# bms_board.net
KiCad netlist of a schematic drawn in EAGLE
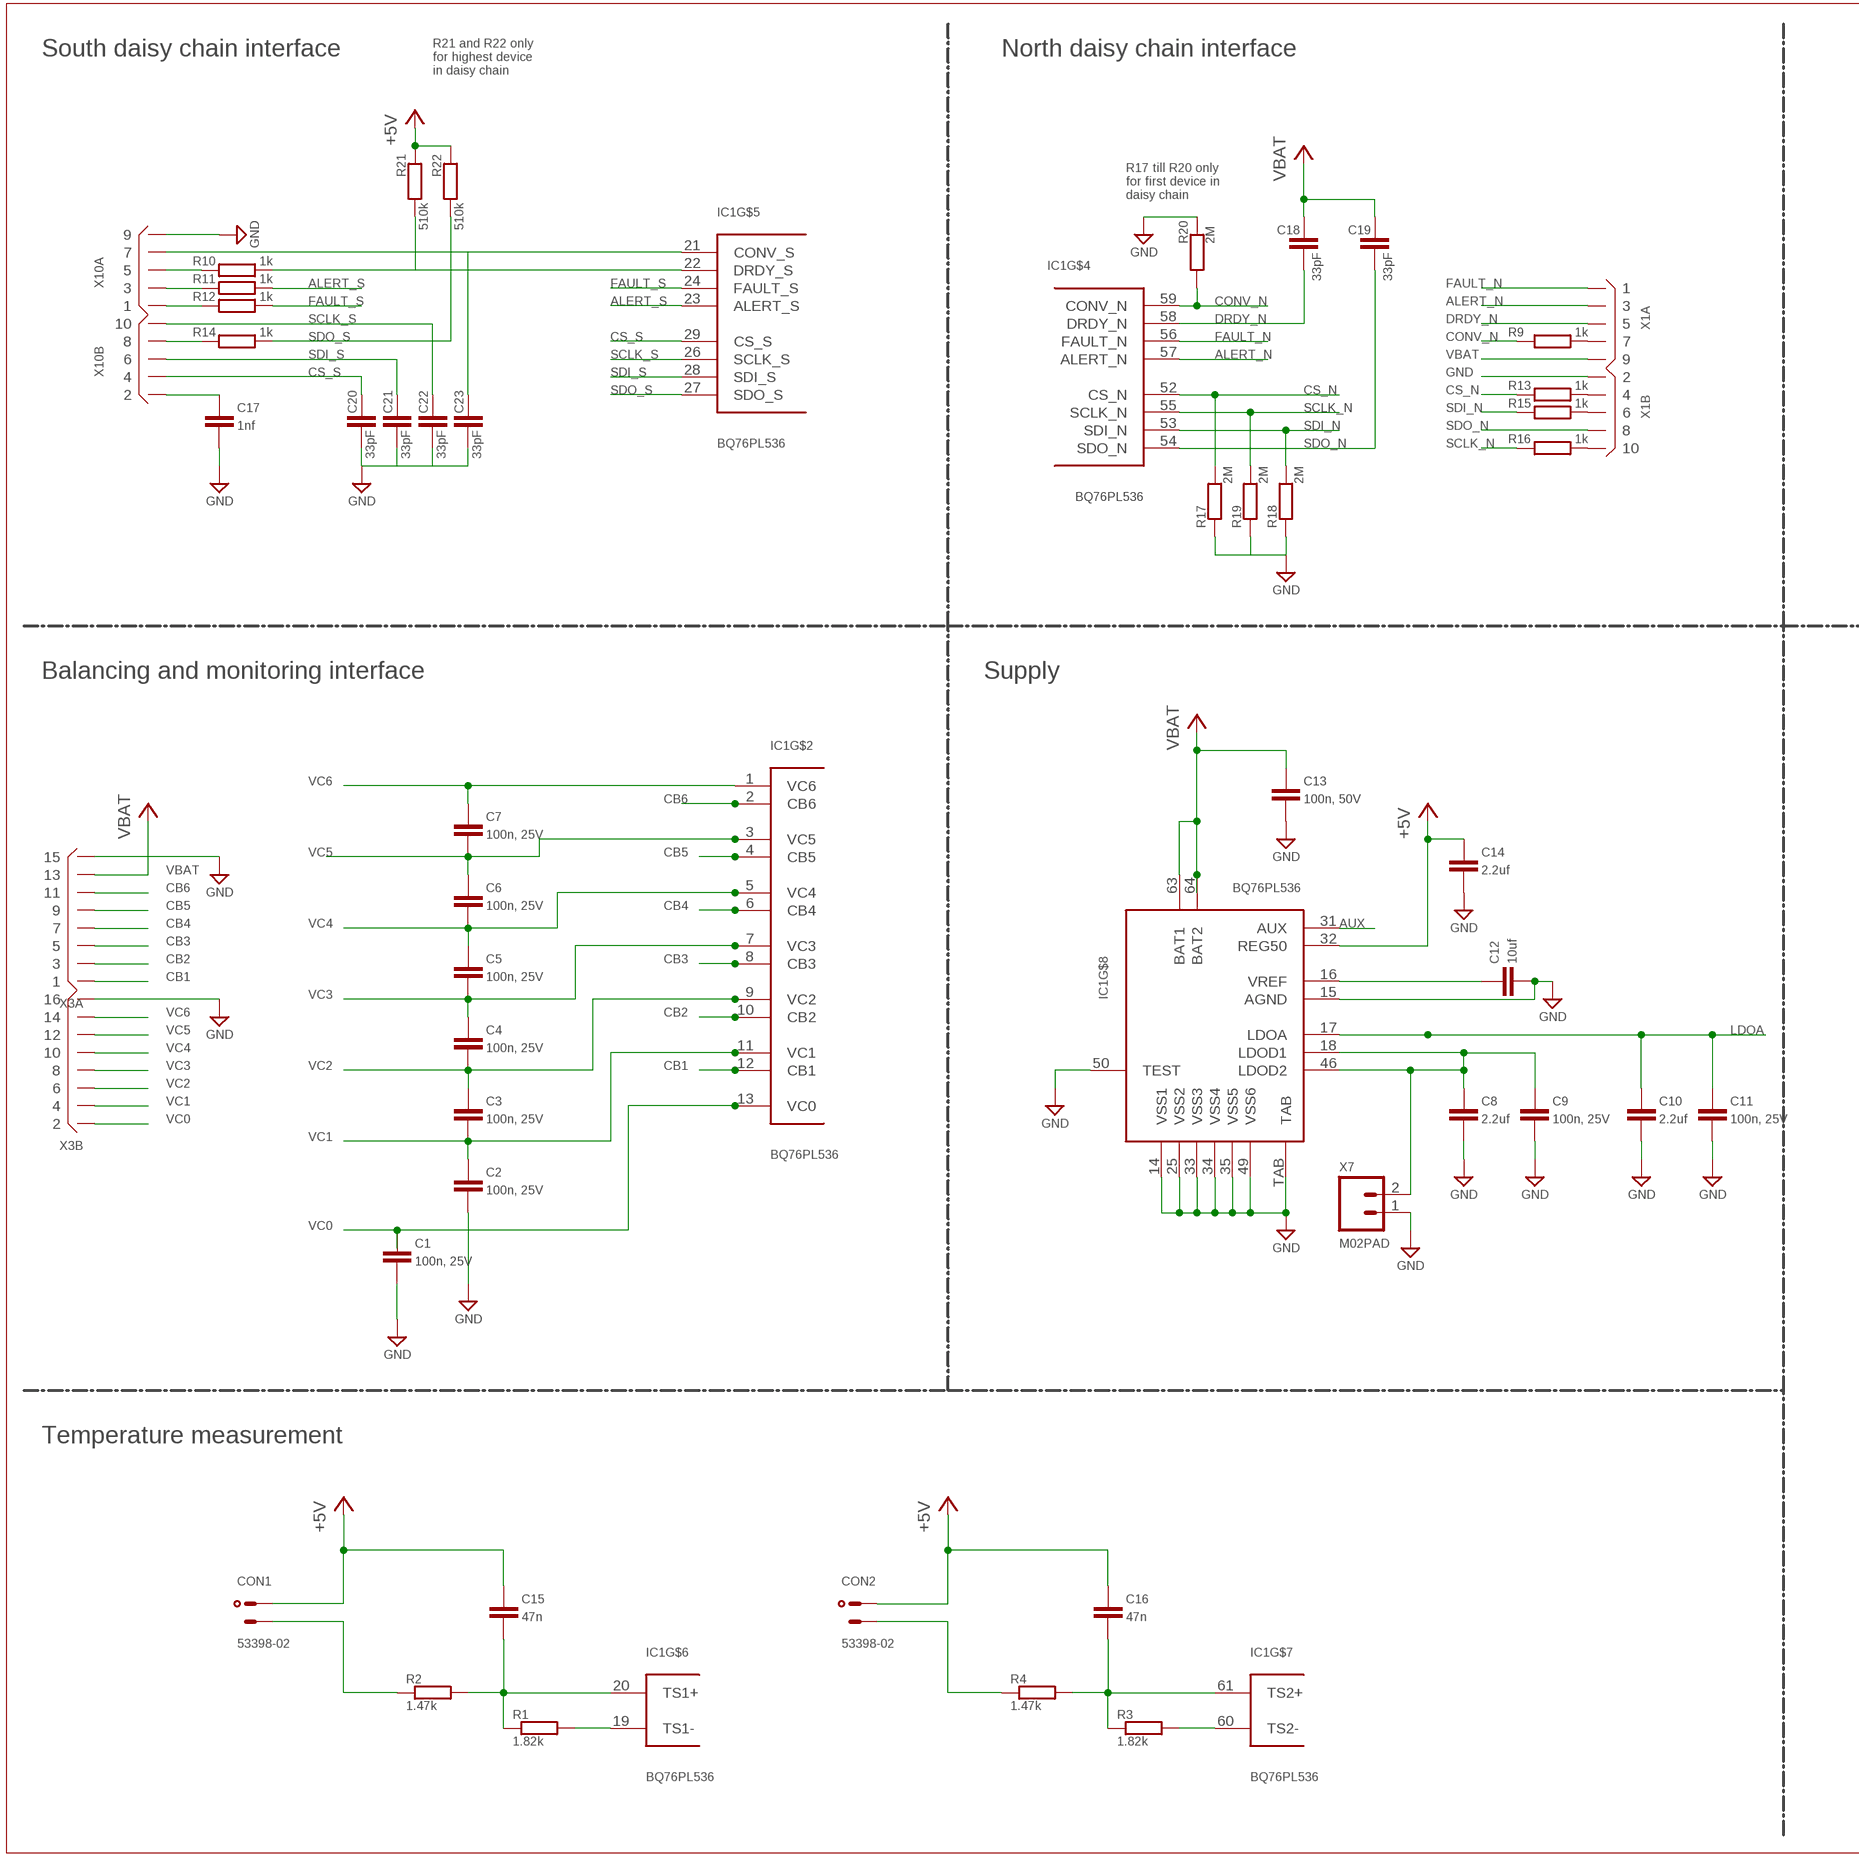
[diagram p0: schematic, sheet 1, part 1 of 2]
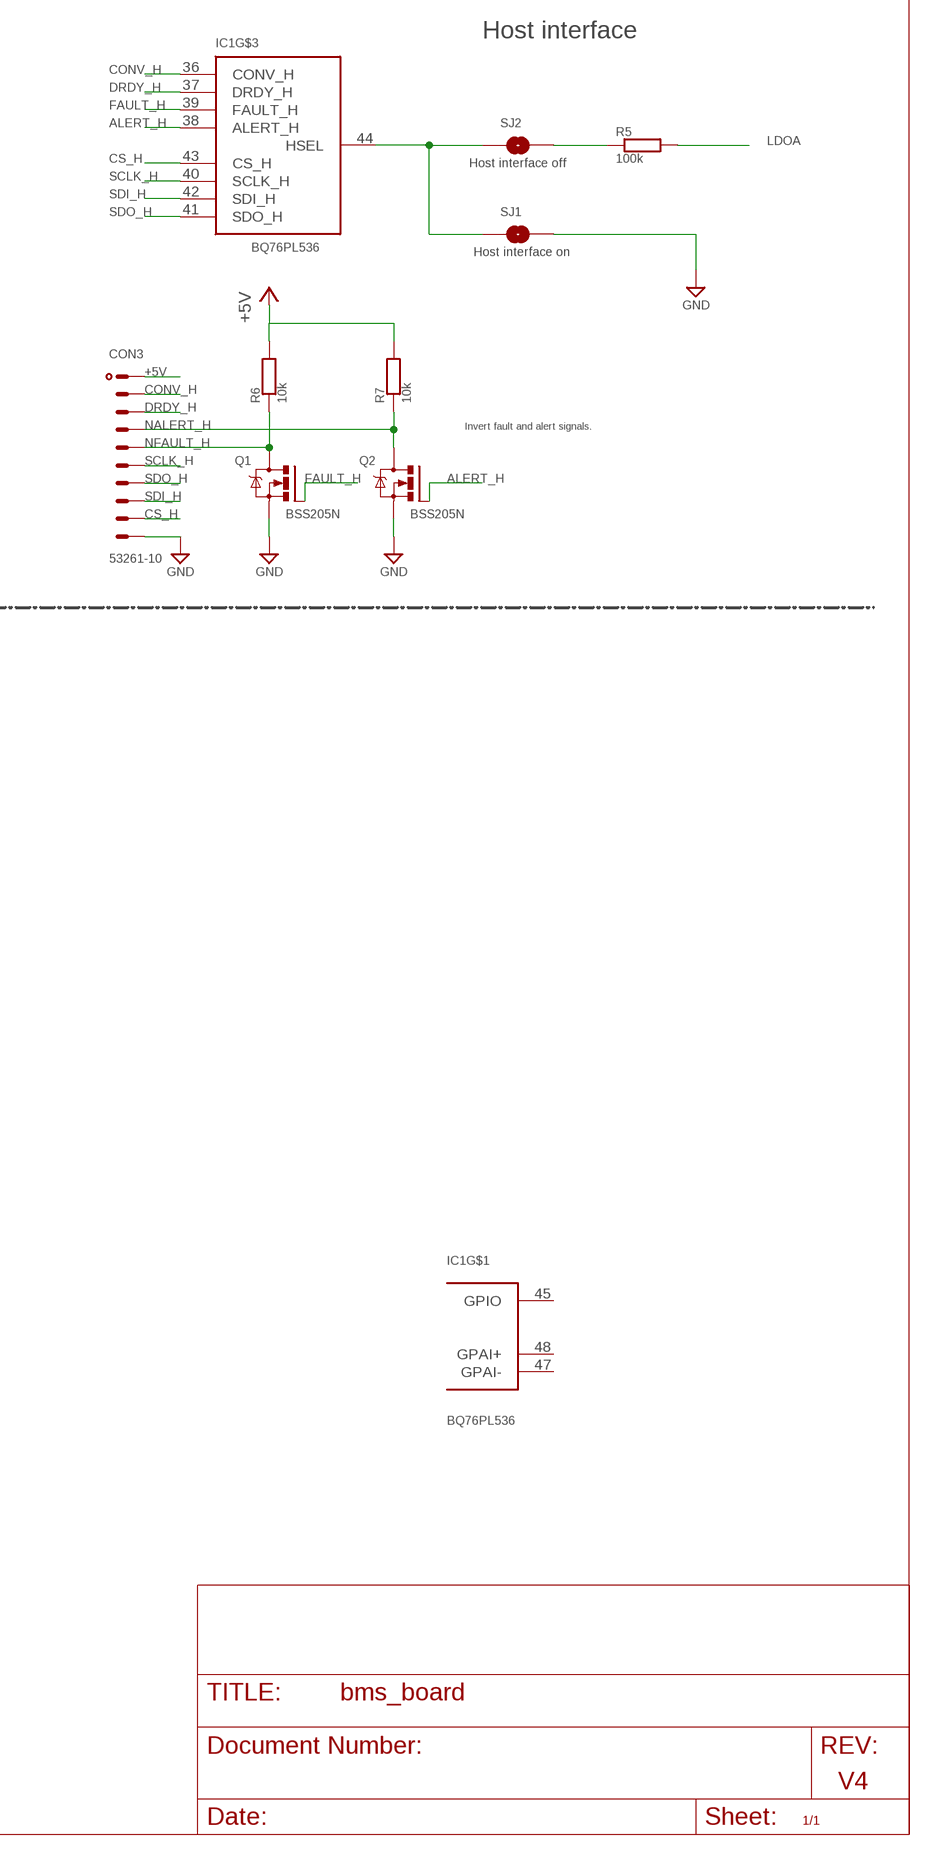
[diagram p1: schematic, sheet 1, part 2 of 2]

(export (version "E")
  (design (tool "Eeschema 10.0.6"))
  (components
    (comp (ref "C1")
      (value "100n, 25V")
      (footprint "eagle-import:C0603")
      (libsource (lib "eagle-import") (part "C0603"))
    )
    (comp (ref "C2")
      (value "100n, 25V")
      (footprint "eagle-import:C0603")
      (libsource (lib "eagle-import") (part "C0603"))
    )
    (comp (ref "C3")
      (value "100n, 25V")
      (footprint "eagle-import:C0603")
      (libsource (lib "eagle-import") (part "C0603"))
    )
    (comp (ref "C4")
      (value "100n, 25V")
      (footprint "eagle-import:C0603")
      (libsource (lib "eagle-import") (part "C0603"))
    )
    (comp (ref "C5")
      (value "100n, 25V")
      (footprint "eagle-import:C0603")
      (libsource (lib "eagle-import") (part "C0603"))
    )
    (comp (ref "C6")
      (value "100n, 25V")
      (footprint "eagle-import:C0603")
      (libsource (lib "eagle-import") (part "C0603"))
    )
    (comp (ref "C7")
      (value "100n, 25V")
      (footprint "eagle-import:C0603")
      (libsource (lib "eagle-import") (part "C0603"))
    )
    (comp (ref "C8")
      (value "2.2uf")
      (footprint "eagle-import:C0805")
      (libsource (lib "eagle-import") (part "CSTD"))
    )
    (comp (ref "C9")
      (value "100n, 25V")
      (footprint "eagle-import:C0805")
      (libsource (lib "eagle-import") (part "CSTD"))
    )
    (comp (ref "C10")
      (value "2.2uf")
      (footprint "eagle-import:C0805")
      (libsource (lib "eagle-import") (part "CSTD"))
    )
    (comp (ref "C11")
      (value "100n, 25V")
      (footprint "eagle-import:C0805")
      (libsource (lib "eagle-import") (part "CSTD"))
    )
    (comp (ref "C12")
      (value "10uf")
      (footprint "eagle-import:C0805")
      (libsource (lib "eagle-import") (part "CSTD"))
    )
    (comp (ref "C13")
      (value "100n, 50V")
      (footprint "eagle-import:C0805")
      (libsource (lib "eagle-import") (part "CSTD"))
    )
    (comp (ref "C14")
      (value "2.2uf")
      (footprint "eagle-import:C0805")
      (libsource (lib "eagle-import") (part "CSTD"))
    )
    (comp (ref "C15")
      (value "47n")
      (footprint "eagle-import:C0805")
      (libsource (lib "eagle-import") (part "CSTD"))
    )
    (comp (ref "C16")
      (value "47n")
      (footprint "eagle-import:C0805")
      (libsource (lib "eagle-import") (part "CSTD"))
    )
    (comp (ref "C17")
      (value "1nf")
      (footprint "eagle-import:C0805")
      (libsource (lib "eagle-import") (part "CSTD"))
    )
    (comp (ref "C18")
      (value "33pF")
      (footprint "eagle-import:C0603")
      (libsource (lib "eagle-import") (part "C0603"))
    )
    (comp (ref "C19")
      (value "33pF")
      (footprint "eagle-import:C0603")
      (libsource (lib "eagle-import") (part "C0603"))
    )
    (comp (ref "C20")
      (value "33pF")
      (footprint "eagle-import:C0603")
      (libsource (lib "eagle-import") (part "C0603"))
    )
    (comp (ref "C21")
      (value "33pF")
      (footprint "eagle-import:C0603")
      (libsource (lib "eagle-import") (part "C0603"))
    )
    (comp (ref "C22")
      (value "33pF")
      (footprint "eagle-import:C0603")
      (libsource (lib "eagle-import") (part "C0603"))
    )
    (comp (ref "C23")
      (value "33pF")
      (footprint "eagle-import:C0603")
      (libsource (lib "eagle-import") (part "C0603"))
    )
    (comp (ref "CON1")
      (value "53398-02")
      (footprint "eagle-import:53398-02")
      (libsource (lib "eagle-import") (part "53?-02398"))
    )
    (comp (ref "CON2")
      (value "53398-02")
      (footprint "eagle-import:53398-02")
      (libsource (lib "eagle-import") (part "53?-02398"))
    )
    (comp (ref "CON3")
      (value "53261-10")
      (footprint "eagle-import:53261-10")
      (libsource (lib "eagle-import") (part "53?-10261"))
    )
    (comp (ref "IC1")
      (value "BQ76PL536")
      (footprint "eagle-import:LQFP-64")
      (libsource (lib "eagle-import") (part "BQ76PL536"))
    )
    (comp (ref "Q1")
      (value "BSS205N")
      (footprint "eagle-import:SOT23")
      (libsource (lib "eagle-import") (part "BSS205N"))
    )
    (comp (ref "Q2")
      (value "BSS205N")
      (footprint "eagle-import:SOT23")
      (libsource (lib "eagle-import") (part "BSS205N"))
    )
    (comp (ref "R1")
      (value "1.82k")
      (footprint "eagle-import:R0805")
      (libsource (lib "eagle-import") (part "R"))
    )
    (comp (ref "R2")
      (value "1.47k")
      (footprint "eagle-import:R0805")
      (libsource (lib "eagle-import") (part "R"))
    )
    (comp (ref "R3")
      (value "1.82k")
      (footprint "eagle-import:R0805")
      (libsource (lib "eagle-import") (part "R"))
    )
    (comp (ref "R4")
      (value "1.47k")
      (footprint "eagle-import:R0805")
      (libsource (lib "eagle-import") (part "R"))
    )
    (comp (ref "R5")
      (value "100k")
      (footprint "eagle-import:R0805")
      (libsource (lib "eagle-import") (part "R"))
    )
    (comp (ref "R6")
      (value "10k")
      (footprint "eagle-import:R0805")
      (libsource (lib "eagle-import") (part "R"))
    )
    (comp (ref "R7")
      (value "10k")
      (footprint "eagle-import:R0805")
      (libsource (lib "eagle-import") (part "R"))
    )
    (comp (ref "R9")
      (value "1k")
      (footprint "eagle-import:R0603")
      (libsource (lib "eagle-import") (part "R0603"))
    )
    (comp (ref "R10")
      (value "1k")
      (footprint "eagle-import:R0603")
      (libsource (lib "eagle-import") (part "R0603"))
    )
    (comp (ref "R11")
      (value "1k")
      (footprint "eagle-import:R0603")
      (libsource (lib "eagle-import") (part "R0603"))
    )
    (comp (ref "R12")
      (value "1k")
      (footprint "eagle-import:R0603")
      (libsource (lib "eagle-import") (part "R0603"))
    )
    (comp (ref "R13")
      (value "1k")
      (footprint "eagle-import:R0603")
      (libsource (lib "eagle-import") (part "R0603"))
    )
    (comp (ref "R14")
      (value "1k")
      (footprint "eagle-import:R0603")
      (libsource (lib "eagle-import") (part "R0603"))
    )
    (comp (ref "R15")
      (value "1k")
      (footprint "eagle-import:R0603")
      (libsource (lib "eagle-import") (part "R0603"))
    )
    (comp (ref "R16")
      (value "1k")
      (footprint "eagle-import:R0603")
      (libsource (lib "eagle-import") (part "R0603"))
    )
    (comp (ref "R17")
      (value "2M")
      (footprint "eagle-import:R0603")
      (libsource (lib "eagle-import") (part "R0603"))
    )
    (comp (ref "R18")
      (value "2M")
      (footprint "eagle-import:R0603")
      (libsource (lib "eagle-import") (part "R0603"))
    )
    (comp (ref "R19")
      (value "2M")
      (footprint "eagle-import:R0603")
      (libsource (lib "eagle-import") (part "R0603"))
    )
    (comp (ref "R20")
      (value "2M")
      (footprint "eagle-import:R0603")
      (libsource (lib "eagle-import") (part "R0603"))
    )
    (comp (ref "R21")
      (value "510k")
      (footprint "eagle-import:R0603")
      (libsource (lib "eagle-import") (part "R0603"))
    )
    (comp (ref "R22")
      (value "510k")
      (footprint "eagle-import:R0603")
      (libsource (lib "eagle-import") (part "R0603"))
    )
    (comp (ref "SJ1")
      (value "SOLDERJUMPERNO")
      (footprint "eagle-import:SJ_2S-NO")
      (libsource (lib "eagle-import") (part "SOLDERJUMPERNO"))
    )
    (comp (ref "SJ2")
      (value "SOLDERJUMPERNO")
      (footprint "eagle-import:SJ_2S-NO")
      (libsource (lib "eagle-import") (part "SOLDERJUMPERNO"))
    )
    (comp (ref "X1")
      (value "X05X2IDC-H")
      (footprint "eagle-import:X10R-IDC-H")
      (libsource (lib "eagle-import") (part "X05X2IDC-H"))
    )
    (comp (ref "X3")
      (value "X08X2DR")
      (footprint "eagle-import:X16R-DIL")
      (libsource (lib "eagle-import") (part "X08X2DR"))
    )
    (comp (ref "X7")
      (value "M02PAD")
      (footprint "eagle-import:1X02")
      (libsource (lib "eagle-import") (part "M02PAD"))
    )
    (comp (ref "X10")
      (value "X05X2IDC-H")
      (footprint "eagle-import:X10R-IDC-H")
      (libsource (lib "eagle-import") (part "X05X2IDC-H"))
    )
  )
  (nets
    (net (code "1") (name "+5V") (class "Default")
      (node (ref "C14") (pin "2") (pinfunction "2_2") (pintype "passive"))
      (node (ref "C15") (pin "2") (pinfunction "2_2") (pintype "passive"))
      (node (ref "C16") (pin "2") (pinfunction "2_2") (pintype "passive"))
      (node (ref "CON1") (pin "1") (pinfunction "1_1") (pintype "passive"))
      (node (ref "CON2") (pin "1") (pinfunction "1_1") (pintype "passive"))
      (node (ref "CON3") (pin "1") (pinfunction "1_1") (pintype "passive"))
      (node (ref "IC1") (pin "32") (pinfunction "REG50_32") (pintype "bidirectional"))
      (node (ref "R21") (pin "2") (pinfunction "2_2") (pintype "passive"))
      (node (ref "R22") (pin "2") (pinfunction "2_2") (pintype "passive"))
      (node (ref "R6") (pin "2") (pinfunction "2_2") (pintype "passive"))
      (node (ref "R7") (pin "2") (pinfunction "2_2") (pintype "passive"))
    )
    (net (code "2") (name "/ALERT_H") (class "Default")
      (node (ref "IC1") (pin "38") (pinfunction "ALERT_H_38") (pintype "bidirectional"))
      (node (ref "Q2") (pin "1") (pinfunction "G_1") (pintype "passive"))
    )
    (net (code "3") (name "/ALERT_N") (class "Default")
      (node (ref "IC1") (pin "57") (pinfunction "ALERT_N_57") (pintype "bidirectional"))
      (node (ref "X1") (pin "3") (pinfunction "3_3") (pintype "bidirectional"))
    )
    (net (code "4") (name "/ALERT_S") (class "Default")
      (node (ref "IC1") (pin "23") (pinfunction "ALERT_S_23") (pintype "bidirectional"))
      (node (ref "R11") (pin "2") (pinfunction "2_2") (pintype "passive"))
    )
    (net (code "5") (name "/AUX") (class "Default")
      (node (ref "IC1") (pin "31") (pinfunction "AUX_31") (pintype "bidirectional"))
    )
    (net (code "6") (name "/CB1") (class "Default")
      (node (ref "IC1") (pin "12") (pinfunction "CB1_12") (pintype "bidirectional"))
      (node (ref "X3") (pin "1") (pinfunction "1_1") (pintype "bidirectional"))
    )
    (net (code "7") (name "/CB2") (class "Default")
      (node (ref "IC1") (pin "10") (pinfunction "CB2_10") (pintype "bidirectional"))
      (node (ref "X3") (pin "3") (pinfunction "3_3") (pintype "bidirectional"))
    )
    (net (code "8") (name "/CB3") (class "Default")
      (node (ref "IC1") (pin "8") (pinfunction "CB3_8") (pintype "bidirectional"))
      (node (ref "X3") (pin "5") (pinfunction "5_5") (pintype "bidirectional"))
    )
    (net (code "9") (name "/CB4") (class "Default")
      (node (ref "IC1") (pin "6") (pinfunction "CB4_6") (pintype "bidirectional"))
      (node (ref "X3") (pin "7") (pinfunction "7_7") (pintype "bidirectional"))
    )
    (net (code "10") (name "/CB5") (class "Default")
      (node (ref "IC1") (pin "4") (pinfunction "CB5_4") (pintype "bidirectional"))
      (node (ref "X3") (pin "9") (pinfunction "9_9") (pintype "bidirectional"))
    )
    (net (code "11") (name "/CB6") (class "Default")
      (node (ref "IC1") (pin "2") (pinfunction "CB6_2") (pintype "bidirectional"))
      (node (ref "X3") (pin "11") (pinfunction "11_11") (pintype "bidirectional"))
    )
    (net (code "12") (name "/CONV_H") (class "Default")
      (node (ref "CON3") (pin "2") (pinfunction "2_2") (pintype "passive"))
      (node (ref "IC1") (pin "36") (pinfunction "CONV_H_36") (pintype "bidirectional"))
    )
    (net (code "13") (name "/CONV_N") (class "Default")
      (node (ref "IC1") (pin "59") (pinfunction "CONV_N_59") (pintype "bidirectional"))
      (node (ref "R20") (pin "2") (pinfunction "2_2") (pintype "passive"))
      (node (ref "R9") (pin "1") (pinfunction "1_1") (pintype "passive"))
    )
    (net (code "14") (name "/CS_H") (class "Default")
      (node (ref "CON3") (pin "9") (pinfunction "9_9") (pintype "passive"))
      (node (ref "IC1") (pin "43") (pinfunction "CS_H_43") (pintype "bidirectional"))
    )
    (net (code "15") (name "/CS_N") (class "Default")
      (node (ref "IC1") (pin "52") (pinfunction "CS_N_52") (pintype "bidirectional"))
      (node (ref "R13") (pin "1") (pinfunction "1_1") (pintype "passive"))
      (node (ref "R17") (pin "2") (pinfunction "2_2") (pintype "passive"))
    )
    (net (code "16") (name "/CS_S") (class "Default")
      (node (ref "C20") (pin "1") (pinfunction "1_1") (pintype "passive"))
      (node (ref "IC1") (pin "29") (pinfunction "CS_S_29") (pintype "bidirectional"))
      (node (ref "X10") (pin "4") (pinfunction "4_4") (pintype "bidirectional"))
    )
    (net (code "17") (name "/DRDY_H") (class "Default")
      (node (ref "CON3") (pin "3") (pinfunction "3_3") (pintype "passive"))
      (node (ref "IC1") (pin "37") (pinfunction "DRDY_H_37") (pintype "bidirectional"))
    )
    (net (code "18") (name "/DRDY_N") (class "Default")
      (node (ref "C18") (pin "2") (pinfunction "2_2") (pintype "passive"))
      (node (ref "IC1") (pin "58") (pinfunction "DRDY_N_58") (pintype "bidirectional"))
      (node (ref "X1") (pin "5") (pinfunction "5_5") (pintype "bidirectional"))
    )
    (net (code "19") (name "/FAULT_H") (class "Default")
      (node (ref "IC1") (pin "39") (pinfunction "FAULT_H_39") (pintype "bidirectional"))
      (node (ref "Q1") (pin "1") (pinfunction "G_1") (pintype "passive"))
    )
    (net (code "20") (name "/FAULT_N") (class "Default")
      (node (ref "IC1") (pin "56") (pinfunction "FAULT_N_56") (pintype "bidirectional"))
      (node (ref "X1") (pin "1") (pinfunction "1_1") (pintype "bidirectional"))
    )
    (net (code "21") (name "/FAULT_S") (class "Default")
      (node (ref "IC1") (pin "24") (pinfunction "FAULT_S_24") (pintype "bidirectional"))
      (node (ref "R12") (pin "2") (pinfunction "2_2") (pintype "passive"))
    )
    (net (code "22") (name "/LDOA") (class "Default")
      (node (ref "C10") (pin "2") (pinfunction "2_2") (pintype "passive"))
      (node (ref "C11") (pin "2") (pinfunction "2_2") (pintype "passive"))
      (node (ref "IC1") (pin "17") (pinfunction "LDOA_17") (pintype "bidirectional"))
      (node (ref "R5") (pin "2") (pinfunction "2_2") (pintype "passive"))
    )
    (net (code "23") (name "/NALERT_H") (class "Default")
      (node (ref "CON3") (pin "4") (pinfunction "4_4") (pintype "passive"))
      (node (ref "Q2") (pin "3") (pinfunction "D_3") (pintype "passive"))
      (node (ref "R7") (pin "1") (pinfunction "1_1") (pintype "passive"))
    )
    (net (code "24") (name "/NFAULT_H") (class "Default")
      (node (ref "CON3") (pin "5") (pinfunction "5_5") (pintype "passive"))
      (node (ref "Q1") (pin "3") (pinfunction "D_3") (pintype "passive"))
      (node (ref "R6") (pin "1") (pinfunction "1_1") (pintype "passive"))
    )
    (net (code "25") (name "/SCLK_H") (class "Default")
      (node (ref "CON3") (pin "6") (pinfunction "6_6") (pintype "passive"))
      (node (ref "IC1") (pin "40") (pinfunction "SCLK_H_40") (pintype "bidirectional"))
    )
    (net (code "26") (name "/SCLK_N") (class "Default")
      (node (ref "IC1") (pin "55") (pinfunction "SCLK_N_55") (pintype "bidirectional"))
      (node (ref "R16") (pin "1") (pinfunction "1_1") (pintype "passive"))
      (node (ref "R19") (pin "2") (pinfunction "2_2") (pintype "passive"))
    )
    (net (code "27") (name "/SCLK_S") (class "Default")
      (node (ref "C22") (pin "1") (pinfunction "1_1") (pintype "passive"))
      (node (ref "IC1") (pin "26") (pinfunction "SCLK_S_26") (pintype "bidirectional"))
      (node (ref "X10") (pin "10") (pinfunction "10_10") (pintype "bidirectional"))
    )
    (net (code "28") (name "/SDI_H") (class "Default")
      (node (ref "CON3") (pin "8") (pinfunction "8_8") (pintype "passive"))
      (node (ref "IC1") (pin "42") (pinfunction "SDI_H_42") (pintype "bidirectional"))
    )
    (net (code "29") (name "/SDI_N") (class "Default")
      (node (ref "IC1") (pin "53") (pinfunction "SDI_N_53") (pintype "bidirectional"))
      (node (ref "R15") (pin "1") (pinfunction "1_1") (pintype "passive"))
      (node (ref "R18") (pin "2") (pinfunction "2_2") (pintype "passive"))
    )
    (net (code "30") (name "/SDI_S") (class "Default")
      (node (ref "C21") (pin "1") (pinfunction "1_1") (pintype "passive"))
      (node (ref "IC1") (pin "28") (pinfunction "SDI_S_28") (pintype "bidirectional"))
      (node (ref "X10") (pin "6") (pinfunction "6_6") (pintype "bidirectional"))
    )
    (net (code "31") (name "/SDO_H") (class "Default")
      (node (ref "CON3") (pin "7") (pinfunction "7_7") (pintype "passive"))
      (node (ref "IC1") (pin "41") (pinfunction "SDO_H_41") (pintype "bidirectional"))
    )
    (net (code "32") (name "/SDO_N") (class "Default")
      (node (ref "C19") (pin "2") (pinfunction "2_2") (pintype "passive"))
      (node (ref "IC1") (pin "54") (pinfunction "SDO_N_54") (pintype "bidirectional"))
      (node (ref "X1") (pin "8") (pinfunction "8_8") (pintype "bidirectional"))
    )
    (net (code "33") (name "/SDO_S") (class "Default")
      (node (ref "IC1") (pin "27") (pinfunction "SDO_S_27") (pintype "bidirectional"))
      (node (ref "R14") (pin "2") (pinfunction "2_2") (pintype "passive"))
      (node (ref "R22") (pin "1") (pinfunction "1_1") (pintype "passive"))
    )
    (net (code "34") (name "/VC0") (class "Default")
      (node (ref "C1") (pin "2") (pinfunction "2_2") (pintype "passive"))
      (node (ref "IC1") (pin "13") (pinfunction "VC0_13") (pintype "bidirectional"))
      (node (ref "X3") (pin "2") (pinfunction "2_2") (pintype "bidirectional"))
    )
    (net (code "35") (name "/VC1") (class "Default")
      (node (ref "C2") (pin "2") (pinfunction "2_2") (pintype "passive"))
      (node (ref "C3") (pin "1") (pinfunction "1_1") (pintype "passive"))
      (node (ref "IC1") (pin "11") (pinfunction "VC1_11") (pintype "bidirectional"))
      (node (ref "X3") (pin "4") (pinfunction "4_4") (pintype "bidirectional"))
    )
    (net (code "36") (name "/VC2") (class "Default")
      (node (ref "C3") (pin "2") (pinfunction "2_2") (pintype "passive"))
      (node (ref "C4") (pin "1") (pinfunction "1_1") (pintype "passive"))
      (node (ref "IC1") (pin "9") (pinfunction "VC2_9") (pintype "bidirectional"))
      (node (ref "X3") (pin "6") (pinfunction "6_6") (pintype "bidirectional"))
    )
    (net (code "37") (name "/VC3") (class "Default")
      (node (ref "C4") (pin "2") (pinfunction "2_2") (pintype "passive"))
      (node (ref "C5") (pin "1") (pinfunction "1_1") (pintype "passive"))
      (node (ref "IC1") (pin "7") (pinfunction "VC3_7") (pintype "bidirectional"))
      (node (ref "X3") (pin "8") (pinfunction "8_8") (pintype "bidirectional"))
    )
    (net (code "38") (name "/VC4") (class "Default")
      (node (ref "C5") (pin "2") (pinfunction "2_2") (pintype "passive"))
      (node (ref "C6") (pin "1") (pinfunction "1_1") (pintype "passive"))
      (node (ref "IC1") (pin "5") (pinfunction "VC4_5") (pintype "bidirectional"))
      (node (ref "X3") (pin "10") (pinfunction "10_10") (pintype "bidirectional"))
    )
    (net (code "39") (name "/VC5") (class "Default")
      (node (ref "C6") (pin "2") (pinfunction "2_2") (pintype "passive"))
      (node (ref "C7") (pin "1") (pinfunction "1_1") (pintype "passive"))
      (node (ref "IC1") (pin "3") (pinfunction "VC5_3") (pintype "bidirectional"))
      (node (ref "X3") (pin "12") (pinfunction "12_12") (pintype "bidirectional"))
    )
    (net (code "40") (name "/VC6") (class "Default")
      (node (ref "C7") (pin "2") (pinfunction "2_2") (pintype "passive"))
      (node (ref "IC1") (pin "1") (pinfunction "VC6_1") (pintype "bidirectional"))
      (node (ref "X3") (pin "14") (pinfunction "14_14") (pintype "bidirectional"))
    )
    (net (code "41") (name "GND") (class "Default")
      (node (ref "C1") (pin "1") (pinfunction "1_1") (pintype "passive"))
      (node (ref "C10") (pin "1") (pinfunction "1_1") (pintype "passive"))
      (node (ref "C11") (pin "1") (pinfunction "1_1") (pintype "passive"))
      (node (ref "C12") (pin "1") (pinfunction "1_1") (pintype "passive"))
      (node (ref "C13") (pin "1") (pinfunction "1_1") (pintype "passive"))
      (node (ref "C14") (pin "1") (pinfunction "1_1") (pintype "passive"))
      (node (ref "C17") (pin "1") (pinfunction "1_1") (pintype "passive"))
      (node (ref "C2") (pin "1") (pinfunction "1_1") (pintype "passive"))
      (node (ref "C20") (pin "2") (pinfunction "2_2") (pintype "passive"))
      (node (ref "C21") (pin "2") (pinfunction "2_2") (pintype "passive"))
      (node (ref "C22") (pin "2") (pinfunction "2_2") (pintype "passive"))
      (node (ref "C23") (pin "2") (pinfunction "2_2") (pintype "passive"))
      (node (ref "C8") (pin "1") (pinfunction "1_1") (pintype "passive"))
      (node (ref "C9") (pin "1") (pinfunction "1_1") (pintype "passive"))
      (node (ref "CON3") (pin "10") (pinfunction "10_10") (pintype "passive"))
      (node (ref "IC1") (pin "14") (pinfunction "VSS1_14") (pintype "bidirectional"))
      (node (ref "IC1") (pin "15") (pinfunction "AGND_15") (pintype "bidirectional"))
      (node (ref "IC1") (pin "25") (pinfunction "VSS2_25") (pintype "bidirectional"))
      (node (ref "IC1") (pin "33") (pinfunction "VSS3_33") (pintype "bidirectional"))
      (node (ref "IC1") (pin "34") (pinfunction "VSS4_34") (pintype "bidirectional"))
      (node (ref "IC1") (pin "35") (pinfunction "VSS5_35") (pintype "bidirectional"))
      (node (ref "IC1") (pin "49") (pinfunction "VSS6_49") (pintype "bidirectional"))
      (node (ref "IC1") (pin "50") (pinfunction "TEST_50") (pintype "bidirectional"))
      (node (ref "IC1") (pin "TAB") (pinfunction "TAB_TAB") (pintype "bidirectional"))
      (node (ref "Q1") (pin "2") (pinfunction "S_2") (pintype "passive"))
      (node (ref "Q2") (pin "2") (pinfunction "S_2") (pintype "passive"))
      (node (ref "R17") (pin "1") (pinfunction "1_1") (pintype "passive"))
      (node (ref "R18") (pin "1") (pinfunction "1_1") (pintype "passive"))
      (node (ref "R19") (pin "1") (pinfunction "1_1") (pintype "passive"))
      (node (ref "R20") (pin "1") (pinfunction "1_1") (pintype "passive"))
      (node (ref "SJ1") (pin "2") (pinfunction "2_2") (pintype "passive"))
      (node (ref "X1") (pin "2") (pinfunction "2_2") (pintype "bidirectional"))
      (node (ref "X10") (pin "9") (pinfunction "9_9") (pintype "bidirectional"))
      (node (ref "X3") (pin "15") (pinfunction "15_15") (pintype "bidirectional"))
      (node (ref "X3") (pin "16") (pinfunction "16_16") (pintype "bidirectional"))
      (node (ref "X7") (pin "1") (pinfunction "1_1") (pintype "passive"))
    )
    (net (code "42") (name "Net-(C17-Pad2)") (class "Default")
      (node (ref "C17") (pin "2") (pinfunction "2_2") (pintype "passive"))
      (node (ref "X10") (pin "2") (pinfunction "2_2") (pintype "bidirectional"))
    )
    (net (code "43") (name "Net-(CON1-Pad2)") (class "Default")
      (node (ref "CON1") (pin "2") (pinfunction "2_2") (pintype "passive"))
      (node (ref "R2") (pin "1") (pinfunction "1_1") (pintype "passive"))
    )
    (net (code "44") (name "Net-(CON2-Pad2)") (class "Default")
      (node (ref "CON2") (pin "2") (pinfunction "2_2") (pintype "passive"))
      (node (ref "R4") (pin "1") (pinfunction "1_1") (pintype "passive"))
    )
    (net (code "45") (name "Net-(IC1C-HSEL)") (class "Default")
      (node (ref "IC1") (pin "44") (pinfunction "HSEL_44") (pintype "bidirectional"))
      (node (ref "SJ1") (pin "1") (pinfunction "1_1") (pintype "passive"))
      (node (ref "SJ2") (pin "1") (pinfunction "1_1") (pintype "passive"))
    )
    (net (code "46") (name "Net-(IC1E-CONV_S)") (class "Default")
      (node (ref "C23") (pin "1") (pinfunction "1_1") (pintype "passive"))
      (node (ref "IC1") (pin "21") (pinfunction "CONV_S_21") (pintype "bidirectional"))
      (node (ref "X10") (pin "7") (pinfunction "7_7") (pintype "bidirectional"))
    )
    (net (code "47") (name "Net-(IC1E-DRDY_S)") (class "Default")
      (node (ref "IC1") (pin "22") (pinfunction "DRDY_S_22") (pintype "bidirectional"))
      (node (ref "R10") (pin "2") (pinfunction "2_2") (pintype "passive"))
      (node (ref "R21") (pin "1") (pinfunction "1_1") (pintype "passive"))
    )
    (net (code "48") (name "Net-(IC1F-TS1+)") (class "Default")
      (node (ref "C15") (pin "1") (pinfunction "1_1") (pintype "passive"))
      (node (ref "IC1") (pin "20") (pinfunction "TS1+_20") (pintype "bidirectional"))
      (node (ref "R1") (pin "1") (pinfunction "1_1") (pintype "passive"))
      (node (ref "R2") (pin "2") (pinfunction "2_2") (pintype "passive"))
    )
    (net (code "49") (name "Net-(IC1F-TS1-)") (class "Default")
      (node (ref "IC1") (pin "19") (pinfunction "TS1-_19") (pintype "bidirectional"))
      (node (ref "R1") (pin "2") (pinfunction "2_2") (pintype "passive"))
    )
    (net (code "50") (name "Net-(IC1G-TS2+)") (class "Default")
      (node (ref "C16") (pin "1") (pinfunction "1_1") (pintype "passive"))
      (node (ref "IC1") (pin "61") (pinfunction "TS2+_61") (pintype "bidirectional"))
      (node (ref "R3") (pin "1") (pinfunction "1_1") (pintype "passive"))
      (node (ref "R4") (pin "2") (pinfunction "2_2") (pintype "passive"))
    )
    (net (code "51") (name "Net-(IC1G-TS2-)") (class "Default")
      (node (ref "IC1") (pin "60") (pinfunction "TS2-_60") (pintype "bidirectional"))
      (node (ref "R3") (pin "2") (pinfunction "2_2") (pintype "passive"))
    )
    (net (code "52") (name "Net-(IC1H-LDOD1)") (class "Default")
      (node (ref "C8") (pin "2") (pinfunction "2_2") (pintype "passive"))
      (node (ref "C9") (pin "2") (pinfunction "2_2") (pintype "passive"))
      (node (ref "IC1") (pin "18") (pinfunction "LDOD1_18") (pintype "bidirectional"))
      (node (ref "IC1") (pin "46") (pinfunction "LDOD2_46") (pintype "bidirectional"))
      (node (ref "X7") (pin "2") (pinfunction "2_2") (pintype "passive"))
    )
    (net (code "53") (name "Net-(IC1H-VREF)") (class "Default")
      (node (ref "C12") (pin "2") (pinfunction "2_2") (pintype "passive"))
      (node (ref "IC1") (pin "16") (pinfunction "VREF_16") (pintype "bidirectional"))
    )
    (net (code "54") (name "Net-(R5-Pad1)") (class "Default")
      (node (ref "R5") (pin "1") (pinfunction "1_1") (pintype "passive"))
      (node (ref "SJ2") (pin "2") (pinfunction "2_2") (pintype "passive"))
    )
    (net (code "55") (name "Net-(R9-Pad2)") (class "Default")
      (node (ref "R9") (pin "2") (pinfunction "2_2") (pintype "passive"))
      (node (ref "X1") (pin "7") (pinfunction "7_7") (pintype "bidirectional"))
    )
    (net (code "56") (name "Net-(R10-Pad1)") (class "Default")
      (node (ref "R10") (pin "1") (pinfunction "1_1") (pintype "passive"))
      (node (ref "X10") (pin "5") (pinfunction "5_5") (pintype "bidirectional"))
    )
    (net (code "57") (name "Net-(R11-Pad1)") (class "Default")
      (node (ref "R11") (pin "1") (pinfunction "1_1") (pintype "passive"))
      (node (ref "X10") (pin "3") (pinfunction "3_3") (pintype "bidirectional"))
    )
    (net (code "58") (name "Net-(R12-Pad1)") (class "Default")
      (node (ref "R12") (pin "1") (pinfunction "1_1") (pintype "passive"))
      (node (ref "X10") (pin "1") (pinfunction "1_1") (pintype "bidirectional"))
    )
    (net (code "59") (name "Net-(R13-Pad2)") (class "Default")
      (node (ref "R13") (pin "2") (pinfunction "2_2") (pintype "passive"))
      (node (ref "X1") (pin "4") (pinfunction "4_4") (pintype "bidirectional"))
    )
    (net (code "60") (name "Net-(R14-Pad1)") (class "Default")
      (node (ref "R14") (pin "1") (pinfunction "1_1") (pintype "passive"))
      (node (ref "X10") (pin "8") (pinfunction "8_8") (pintype "bidirectional"))
    )
    (net (code "61") (name "Net-(R15-Pad2)") (class "Default")
      (node (ref "R15") (pin "2") (pinfunction "2_2") (pintype "passive"))
      (node (ref "X1") (pin "6") (pinfunction "6_6") (pintype "bidirectional"))
    )
    (net (code "62") (name "Net-(R16-Pad2)") (class "Default")
      (node (ref "R16") (pin "2") (pinfunction "2_2") (pintype "passive"))
      (node (ref "X1") (pin "10") (pinfunction "10_10") (pintype "bidirectional"))
    )
    (net (code "63") (name "VBAT") (class "Default")
      (node (ref "C13") (pin "2") (pinfunction "2_2") (pintype "passive"))
      (node (ref "C18") (pin "1") (pinfunction "1_1") (pintype "passive"))
      (node (ref "C19") (pin "1") (pinfunction "1_1") (pintype "passive"))
      (node (ref "IC1") (pin "63") (pinfunction "BAT1_63") (pintype "bidirectional"))
      (node (ref "IC1") (pin "64") (pinfunction "BAT2_64") (pintype "bidirectional"))
      (node (ref "X1") (pin "9") (pinfunction "9_9") (pintype "bidirectional"))
      (node (ref "X3") (pin "13") (pinfunction "13_13") (pintype "bidirectional"))
    )
    (net (code "64") (name "unconnected-(IC1A-GPAI+-Pad48)") (class "Default")
      (node (ref "IC1") (pin "48") (pinfunction "GPAI+_48") (pintype "bidirectional"))
    )
    (net (code "65") (name "unconnected-(IC1A-GPAI--Pad47)") (class "Default")
      (node (ref "IC1") (pin "47") (pinfunction "GPAI-_47") (pintype "bidirectional"))
    )
    (net (code "66") (name "unconnected-(IC1A-GPIO-Pad45)") (class "Default")
      (node (ref "IC1") (pin "45") (pinfunction "GPIO_45") (pintype "bidirectional"))
    )
  )
)
